# 2_mpcie.net
KiCad netlist of a schematic drawn in Altium Designer
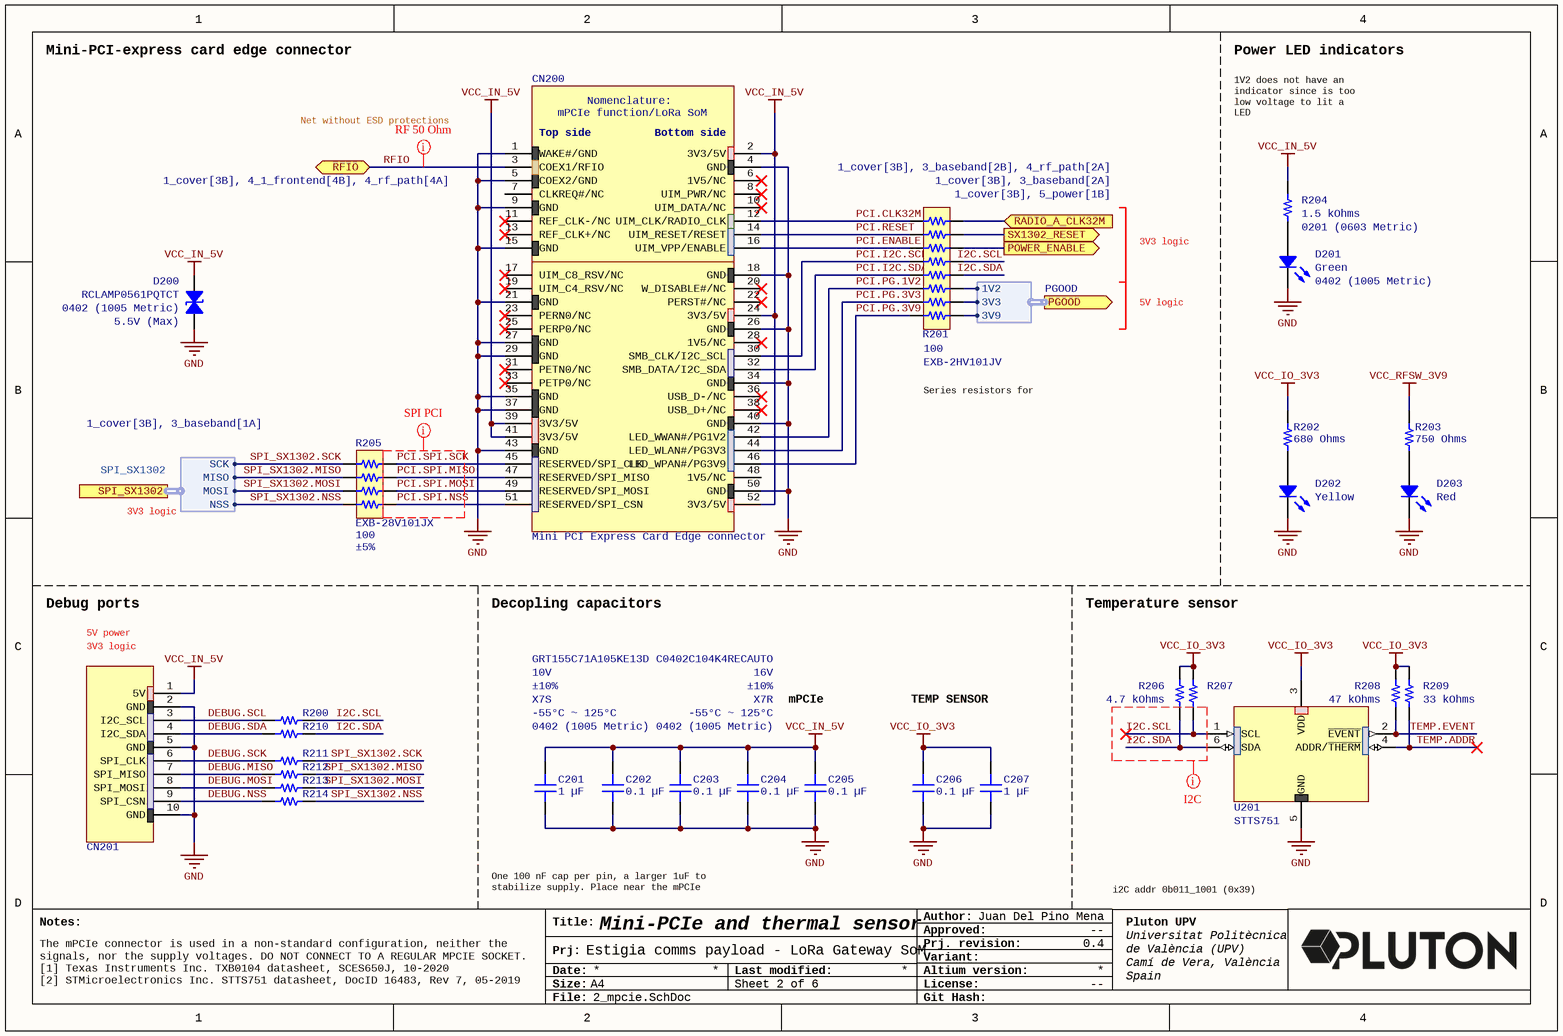
[diagram p0: 2_mpcie.SchDoc]

(export (version "E")
  (design (tool "Eeschema 10.0.6"))
  (components
    (comp (ref "C201")
      (value "1 µF")
      (footprint "CAP 0402_1005")
      (description "CAP CER 1UF 10V X7S 0402")
      (fields
        (field (name "PART NUMBER") "GRT155C71A105KE13D")
        (field (name "DEVICE PACKAGE") "0402 (1005 Metric)")
        (field (name "MANUFACTURER") "Murata Electronics")
        (field (name "OPERATING TEMPERATURE") "-55°C ~ 125°C")
        (field (name "TEMPERATURE COEFFICIENT") "X7S")
        (field (name "TOLERANCE") "±10%")
        (field (name "VOLTAGE - RATED") "10V")
      )
      (libsource (lib "Celestial Altium Library - altium_library") (part "Capacitor"))
    )
    (comp (ref "C202")
      (value "0.1 µF")
      (footprint "CAP 0402_1005")
      (description "CAP CER 0402 0.1UF 16V X7R 10%")
      (fields
        (field (name "PART NUMBER") "C0402C104K4RECAUTO")
        (field (name "MANUFACTURER") "KEMET")
        (field (name "OPERATING TEMPERATURE") "-55°C ~ 125°C")
        (field (name "PACKAGE / CASE") "0402 (1005 Metric)")
        (field (name "TEMPERATURE COEFFICIENT") "X7R")
        (field (name "TOLERANCE") "±10%")
        (field (name "VOLTAGE - RATED") "16V")
      )
      (libsource (lib "Celestial Altium Library - altium_library") (part "Capacitor"))
    )
    (comp (ref "C203")
      (value "0.1 µF")
      (footprint "CAP 0402_1005")
      (description "CAP CER 0402 0.1UF 16V X7R 10%")
      (fields (field (name "PART NUMBER") "C0402C104K4RECAUTO") (field (name "MANUFACTURER") "KEMET"))
      (libsource (lib "Celestial Altium Library - altium_library") (part "Capacitor"))
    )
    (comp (ref "C204")
      (value "0.1 µF")
      (footprint "CAP 0402_1005")
      (description "CAP CER 0402 0.1UF 16V X7R 10%")
      (fields (field (name "PART NUMBER") "C0402C104K4RECAUTO") (field (name "MANUFACTURER") "KEMET"))
      (libsource (lib "Celestial Altium Library - altium_library") (part "Capacitor"))
    )
    (comp (ref "C205")
      (value "0.1 µF")
      (footprint "CAP 0402_1005")
      (description "CAP CER 0402 0.1UF 16V X7R 10%")
      (fields (field (name "PART NUMBER") "C0402C104K4RECAUTO") (field (name "MANUFACTURER") "KEMET"))
      (libsource (lib "Celestial Altium Library - altium_library") (part "Capacitor"))
    )
    (comp (ref "C206")
      (value "0.1 µF")
      (footprint "CAP 0402_1005")
      (description "CAP CER 0402 0.1UF 16V X7R 10%")
      (fields (field (name "PART NUMBER") "C0402C104K4RECAUTO") (field (name "MANUFACTURER") "KEMET"))
      (libsource (lib "Celestial Altium Library - altium_library") (part "Capacitor"))
    )
    (comp (ref "C207")
      (value "1 µF")
      (footprint "CAP 0402_1005")
      (description "CAP CER 1UF 10V X7S 0402")
      (fields
        (field (name "PART NUMBER") "GRT155C71A105KE13D")
        (field (name "MANUFACTURER") "Murata Electronics")
      )
      (libsource (lib "Celestial Altium Library - altium_library") (part "Capacitor"))
    )
    (comp (ref "CN200")
      (value "Mini PCI Express Card Edge connector")
      (footprint "mpcie:Mini PCI Express")
      (libsource (lib "mpcie") (part "MiniPCIe Card"))
    )
    (comp (ref "CN201")
      (value "~")
      (footprint "connectors:header 1x10 2.54mm")
      (description "Specific debug port for the LoRa gateway SoM")
      (libsource (lib "connectors") (part "SoM debug header"))
    )
    (comp (ref "D200")
      (value "RCLAMP0561PQTCT")
      (footprint "0402")
      (description "1-LINE 5V 0.15PF 1.1R ESD SLP100")
      (fields
        (field (name "PART NUMBER") "RCLAMP0561PQTCT")
        (field (name "DEVICE PACKAGE") "0402 (1005 Metric)")
        (field (name "MANUFACTURER") "Semtech Corporation")
        (field (name "VOLTAGE - REVERSE STANDOFF (TYP)") "5.5V (Max)")
      )
      (libsource (lib "Celestial Altium Library - altium_library") (part "Diode TVS"))
    )
    (comp (ref "D201")
      (value "Green")
      (footprint "LED 0402_1005 GREEN")
      (description "LED GREEN CLEAR 2SMD")
      (fields
        (field (name "PART NUMBER") "EAST10052GA0")
        (field (name "COLOR") "Green")
        (field (name "DEVICE PACKAGE") "0402 (1005 Metric)")
        (field (name "MANUFACTURER") "Everlight Electronics Co Ltd")
      )
      (libsource (lib "Celestial Altium Library - altium_library") (part "LED"))
    )
    (comp (ref "D202")
      (value "Yellow")
      (footprint "LED 0402_1005 YELLOW")
      (description "LED YELLOW CLEAR 1005 SMD")
      (fields
        (field (name "PART NUMBER") "FHY1105P-TR")
        (field (name "COLOR") "Yellow")
        (field (name "MANUFACTURER") "Stanley Electric Co")
      )
      (libsource (lib "Celestial Altium Library - altium_library") (part "LED"))
    )
    (comp (ref "D203")
      (value "Red")
      (footprint "LED 0402_1005 RED")
      (description "LED RED CLEAR 2SMD")
      (fields
        (field (name "PART NUMBER") "EAST10053RA0")
        (field (name "COLOR") "Red")
        (field (name "MANUFACTURER") "Everlight Electronics Co Ltd")
      )
      (libsource (lib "Celestial Altium Library - altium_library") (part "LED"))
    )
    (comp (ref "R200")
      (value "0 Ohms")
      (footprint "RES 0201_0603")
      (description "RES SMD 0 OHM JUMPER 1/20W 0201")
      (fields (field (name "PART NUMBER") "AC0201JR-070RL") (field (name "MANUFACTURER") "Yageo"))
      (libsource (lib "Celestial Altium Library - altium_library") (part "Resistor"))
    )
    (comp (ref "R201")
      (value "EXB-2HV101JV")
      (footprint "RESNET 1506-16 CONVEX")
      (description "RES ARRAY 8 RES 100 OHM 1506")
      (fields
        (field (name "PART NUMBER") "EXB-2HV101JV")
        (field (name "MANUFACTURER") "Panasonic Electronic Components")
        (field (name "RESISTANCE (OHMS)") "100")
        (field (name "TOLERANCE") "±5%")
      )
      (libsource (lib "Celestial Altium Library - altium_library") (part "Resistor Array (8 Circuit)"))
    )
    (comp (ref "R202")
      (value "680 Ohms")
      (footprint "RES 0201_0603")
      (description "RES 680 OHM 5% 1/20W 0201")
      (fields (field (name "PART NUMBER") "RC0201JR-07680RL") (field (name "MANUFACTURER") "Yageo"))
      (libsource (lib "Celestial Altium Library - altium_library") (part "Resistor"))
    )
    (comp (ref "R203")
      (value "750 Ohms")
      (footprint "RES 0201_0603")
      (description "RES 750 OHM 5% 1/20W 0201")
      (fields (field (name "PART NUMBER") "RC0201JR-07750RL") (field (name "MANUFACTURER") "Yageo"))
      (libsource (lib "Celestial Altium Library - altium_library") (part "Resistor"))
    )
    (comp (ref "R204")
      (value "1.5 kOhms")
      (footprint "RES 0201_0603")
      (description "RES SMD 1.5K OHM 5% 1/20W 0201")
      (fields
        (field (name "PART NUMBER") "CRCW02011K50JNED")
        (field (name "DEVICE PACKAGE") "0201 (0603 Metric)")
        (field (name "MANUFACTURER") "Vishay Dale")
      )
      (libsource (lib "Celestial Altium Library - altium_library") (part "Resistor"))
    )
    (comp (ref "R205")
      (value "EXB-28V101JX")
      (footprint "RESNET 0804-8 CONVEX")
      (description "RES ARRAY 4 RES 100 OHM 0804")
      (fields
        (field (name "MANUFACTURER") "Panasonic Electronic Components")
        (field (name "PART NUMBER") "EXB-28V101JX")
        (field (name "RESISTANCE (OHMS)") "100")
        (field (name "TOLERANCE") "±5%")
      )
      (libsource (lib "passives") (part "Resistor Array (4 circuit)"))
    )
    (comp (ref "R206")
      (value "4.7 kOhms")
      (footprint "RES 0201_0603")
      (description "RES SMD 4.7K OHM 1% 1/20W 0201")
      (fields (field (name "PART NUMBER") "AC0201FR-074K7L") (field (name "MANUFACTURER") "Yageo"))
      (libsource (lib "Celestial Altium Library - altium_library") (part "Resistor"))
    )
    (comp (ref "R207")
      (value "4.7 kOhms")
      (footprint "RES 0201_0603")
      (description "RES SMD 4.7K OHM 1% 1/20W 0201")
      (fields (field (name "PART NUMBER") "AC0201FR-074K7L") (field (name "MANUFACTURER") "Yageo"))
      (libsource (lib "Celestial Altium Library - altium_library") (part "Resistor"))
    )
    (comp (ref "R208")
      (value "47 kOhms")
      (footprint "RES 0201_0603")
      (description "RES SMD 47K OHM 1% 1/20W 0201")
      (fields (field (name "PART NUMBER") "AC0201FR-0747KL") (field (name "MANUFACTURER") "Yageo"))
      (libsource (lib "Celestial Altium Library - altium_library") (part "Resistor"))
    )
    (comp (ref "R209")
      (value "33 kOhms")
      (footprint "RES 0201_0603")
      (description "RES SMD 33K OHM 1% 1/20W 0201")
      (fields (field (name "PART NUMBER") "CRCW020133K0FKED") (field (name "MANUFACTURER") "Vishay Dale"))
      (libsource (lib "Celestial Altium Library - altium_library") (part "Resistor"))
    )
    (comp (ref "R210")
      (value "0 Ohms")
      (footprint "RES 0201_0603")
      (description "RES SMD 0 OHM JUMPER 1/20W 0201")
      (fields (field (name "PART NUMBER") "AC0201JR-070RL") (field (name "MANUFACTURER") "Yageo"))
      (libsource (lib "Celestial Altium Library - altium_library") (part "Resistor"))
    )
    (comp (ref "R211")
      (value "0 Ohms")
      (footprint "RES 0201_0603")
      (description "RES SMD 0 OHM JUMPER 1/20W 0201")
      (fields (field (name "PART NUMBER") "AC0201JR-070RL") (field (name "MANUFACTURER") "Yageo"))
      (libsource (lib "Celestial Altium Library - altium_library") (part "Resistor"))
    )
    (comp (ref "R212")
      (value "0 Ohms")
      (footprint "RES 0201_0603")
      (description "RES SMD 0 OHM JUMPER 1/20W 0201")
      (fields (field (name "PART NUMBER") "AC0201JR-070RL") (field (name "MANUFACTURER") "Yageo"))
      (libsource (lib "Celestial Altium Library - altium_library") (part "Resistor"))
    )
    (comp (ref "R213")
      (value "0 Ohms")
      (footprint "RES 0201_0603")
      (description "RES SMD 0 OHM JUMPER 1/20W 0201")
      (fields (field (name "PART NUMBER") "AC0201JR-070RL") (field (name "MANUFACTURER") "Yageo"))
      (libsource (lib "Celestial Altium Library - altium_library") (part "Resistor"))
    )
    (comp (ref "R214")
      (value "0 Ohms")
      (footprint "RES 0201_0603")
      (description "RES SMD 0 OHM JUMPER 1/20W 0201")
      (fields (field (name "PART NUMBER") "AC0201JR-070RL") (field (name "MANUFACTURER") "Yageo"))
      (libsource (lib "Celestial Altium Library - altium_library") (part "Resistor"))
    )
    (comp (ref "U201")
      (value "STTS751")
      (footprint "ics:UDFN-6L")
      (description "2.25 V low-voltage local digital temperature sensor")
      (libsource (lib "sensors") (part "STTS751"))
    )
  )
  (nets
    (net (code "3") (name "/1V2") (class "Default")
      (node (ref "R201") (pin "11") (pinfunction "11_11") (pintype "passive"))
    )
    (net (code "4") (name "/3V3") (class "Default")
      (node (ref "R201") (pin "10") (pinfunction "10_10") (pintype "passive"))
    )
    (net (code "5") (name "/3V9") (class "Default")
      (node (ref "R201") (pin "9") (pinfunction "9_9") (pintype "passive"))
    )
    (net (code "6") (name "/DEBUG.MISO") (class "Default")
      (node (ref "CN201") (pin "7") (pinfunction "SPI_MISO_7") (pintype "passive"))
      (node (ref "R212") (pin "1") (pinfunction "1_1") (pintype "passive"))
    )
    (net (code "7") (name "/DEBUG.MOSI") (class "Default")
      (node (ref "CN201") (pin "8") (pinfunction "SPI_MOSI_8") (pintype "passive"))
      (node (ref "R213") (pin "1") (pinfunction "1_1") (pintype "passive"))
    )
    (net (code "8") (name "/DEBUG.NSS") (class "Default")
      (node (ref "CN201") (pin "9") (pinfunction "SPI_CSN_9") (pintype "passive"))
      (node (ref "R214") (pin "1") (pinfunction "1_1") (pintype "passive"))
    )
    (net (code "9") (name "/DEBUG.SCK") (class "Default")
      (node (ref "CN201") (pin "6") (pinfunction "SPI_CLK_6") (pintype "passive"))
      (node (ref "R211") (pin "1") (pinfunction "1_1") (pintype "passive"))
    )
    (net (code "10") (name "/DEBUG.SCL") (class "Default")
      (node (ref "CN201") (pin "3") (pinfunction "I2C_SCL_3") (pintype "passive"))
      (node (ref "R200") (pin "1") (pinfunction "1_1") (pintype "passive"))
    )
    (net (code "11") (name "/DEBUG.SDA") (class "Default")
      (node (ref "CN201") (pin "4") (pinfunction "I2C_SDA_4") (pintype "passive"))
      (node (ref "R210") (pin "1") (pinfunction "1_1") (pintype "passive"))
    )
    (net (code "12") (name "/I2C.SCL") (class "Default")
      (node (ref "R200") (pin "2") (pinfunction "2_2") (pintype "passive"))
      (node (ref "R201") (pin "13") (pinfunction "13_13") (pintype "passive"))
      (node (ref "R207") (pin "1") (pinfunction "1_1") (pintype "passive"))
      (node (ref "U201") (pin "1") (pinfunction "SCL_1") (pintype "input"))
    )
    (net (code "13") (name "/I2C.SDA") (class "Default")
      (node (ref "R201") (pin "12") (pinfunction "12_12") (pintype "passive"))
      (node (ref "R206") (pin "1") (pinfunction "1_1") (pintype "passive"))
      (node (ref "R210") (pin "2") (pinfunction "2_2") (pintype "passive"))
      (node (ref "U201") (pin "6") (pinfunction "SDA_6") (pintype "bidirectional"))
    )
    (net (code "14") (name "/PCI.CLK32M") (class "Default")
      (node (ref "CN200") (pin "12") (pinfunction "UIM_CLK/RADIO_CLK_12") (pintype "passive"))
      (node (ref "R201") (pin "1") (pinfunction "1_1") (pintype "passive"))
    )
    (net (code "15") (name "/PCI.ENABLE") (class "Default")
      (node (ref "CN200") (pin "16") (pinfunction "UIM_VPP/ENABLE_16") (pintype "passive"))
      (node (ref "R201") (pin "3") (pinfunction "3_3") (pintype "passive"))
    )
    (net (code "16") (name "/PCI.I2C.SCL") (class "Default")
      (node (ref "CN200") (pin "30") (pinfunction "SMB_CLK/I2C_SCL_30") (pintype "passive"))
      (node (ref "R201") (pin "4") (pinfunction "4_4") (pintype "passive"))
    )
    (net (code "17") (name "/PCI.I2C.SDA") (class "Default")
      (node (ref "CN200") (pin "32") (pinfunction "SMB_DATA/I2C_SDA_32") (pintype "passive"))
      (node (ref "R201") (pin "5") (pinfunction "6_5") (pintype "passive"))
    )
    (net (code "18") (name "/PCI.PG.1V2") (class "Default")
      (node (ref "CN200") (pin "42") (pinfunction "LED_WWAN#/PG1V2_42") (pintype "passive"))
      (node (ref "R201") (pin "6") (pinfunction "6_6") (pintype "passive"))
    )
    (net (code "19") (name "/PCI.PG.3V3") (class "Default")
      (node (ref "CN200") (pin "44") (pinfunction "LED_WLAN#/PG3V3_44") (pintype "passive"))
      (node (ref "R201") (pin "7") (pinfunction "7_7") (pintype "passive"))
    )
    (net (code "20") (name "/PCI.PG.3V9") (class "Default")
      (node (ref "CN200") (pin "46") (pinfunction "LED_WPAN#/PG3V9_46") (pintype "passive"))
      (node (ref "R201") (pin "8") (pinfunction "8_8") (pintype "passive"))
    )
    (net (code "21") (name "/PCI.RESET") (class "Default")
      (node (ref "CN200") (pin "14") (pinfunction "UIM_RESET/RESET_14") (pintype "passive"))
      (node (ref "R201") (pin "2") (pinfunction "2_2") (pintype "passive"))
    )
    (net (code "22") (name "/PCI.SPI.MISO") (class "Default")
      (node (ref "CN200") (pin "47") (pinfunction "RESERVED/SPI_MISO_47") (pintype "passive"))
      (node (ref "R205") (pin "6") (pinfunction "6_6") (pintype "passive"))
    )
    (net (code "23") (name "/PCI.SPI.MOSI") (class "Default")
      (node (ref "CN200") (pin "49") (pinfunction "RESERVED/SPI_MOSI_49") (pintype "passive"))
      (node (ref "R205") (pin "7") (pinfunction "7_7") (pintype "passive"))
    )
    (net (code "24") (name "/PCI.SPI.NSS") (class "Default")
      (node (ref "CN200") (pin "51") (pinfunction "RESERVED/SPI_CSN_51") (pintype "passive"))
      (node (ref "R205") (pin "8") (pinfunction "8_8") (pintype "passive"))
    )
    (net (code "25") (name "/PCI.SPI.SCK") (class "Default")
      (node (ref "CN200") (pin "45") (pinfunction "RESERVED/SPI_CLK_45") (pintype "passive"))
      (node (ref "R205") (pin "5") (pinfunction "5_5") (pintype "passive"))
    )
    (net (code "26") (name "/POWER_ENABLE") (class "Default")
      (node (ref "R201") (pin "14") (pinfunction "14_14") (pintype "passive"))
    )
    (net (code "27") (name "/RADIO_A_CLK32M") (class "Default")
      (node (ref "R201") (pin "16") (pinfunction "16_16") (pintype "passive"))
    )
    (net (code "28") (name "/RFIO") (class "Default")
      (node (ref "CN200") (pin "3") (pinfunction "COEX1/RFIO_3") (pintype "passive"))
    )
    (net (code "29") (name "/SPI_SX1302.MISO") (class "Default")
      (node (ref "R205") (pin "3") (pinfunction "3_3") (pintype "passive"))
      (node (ref "R212") (pin "2") (pinfunction "2_2") (pintype "passive"))
    )
    (net (code "30") (name "/SPI_SX1302.MOSI") (class "Default")
      (node (ref "R205") (pin "2") (pinfunction "2_2") (pintype "passive"))
      (node (ref "R213") (pin "2") (pinfunction "2_2") (pintype "passive"))
    )
    (net (code "31") (name "/SPI_SX1302.NSS") (class "Default")
      (node (ref "R205") (pin "1") (pinfunction "1_1") (pintype "passive"))
      (node (ref "R214") (pin "2") (pinfunction "2_2") (pintype "passive"))
    )
    (net (code "32") (name "/SPI_SX1302.SCK") (class "Default")
      (node (ref "R205") (pin "4") (pinfunction "4_4") (pintype "passive"))
      (node (ref "R211") (pin "2") (pinfunction "2_2") (pintype "passive"))
    )
    (net (code "33") (name "/SX1302_RESET") (class "Default")
      (node (ref "R201") (pin "15") (pinfunction "15_15") (pintype "passive"))
    )
    (net (code "34") (name "/TEMP.ADDR") (class "Default")
      (node (ref "R209") (pin "1") (pinfunction "1_1") (pintype "passive"))
      (node (ref "U201") (pin "4") (pinfunction "ADDR/~{THERM}_4") (pintype "bidirectional"))
    )
    (net (code "35") (name "/TEMP.EVENT") (class "Default")
      (node (ref "R208") (pin "1") (pinfunction "1_1") (pintype "passive"))
      (node (ref "U201") (pin "2") (pinfunction "~{EVENT}_2") (pintype "output"))
    )
    (net (code "38") (name "GND") (class "Default")
      (node (ref "C201") (pin "1") (pinfunction "1_1") (pintype "passive"))
      (node (ref "C202") (pin "1") (pinfunction "1_1") (pintype "passive"))
      (node (ref "C203") (pin "1") (pinfunction "1_1") (pintype "passive"))
      (node (ref "C204") (pin "1") (pinfunction "1_1") (pintype "passive"))
      (node (ref "C205") (pin "1") (pinfunction "1_1") (pintype "passive"))
      (node (ref "C206") (pin "1") (pinfunction "1_1") (pintype "passive"))
      (node (ref "C207") (pin "1") (pinfunction "1_1") (pintype "passive"))
      (node (ref "CN200") (pin "1") (pinfunction "WAKE#/GND_1") (pintype "passive"))
      (node (ref "CN200") (pin "15") (pinfunction "GND_15") (pintype "power_in"))
      (node (ref "CN200") (pin "18") (pinfunction "GND_18") (pintype "power_in"))
      (node (ref "CN200") (pin "21") (pinfunction "GND_21") (pintype "power_in"))
      (node (ref "CN200") (pin "26") (pinfunction "GND_26") (pintype "power_in"))
      (node (ref "CN200") (pin "27") (pinfunction "GND_27") (pintype "power_in"))
      (node (ref "CN200") (pin "29") (pinfunction "GND_29") (pintype "power_in"))
      (node (ref "CN200") (pin "34") (pinfunction "GND_34") (pintype "power_in"))
      (node (ref "CN200") (pin "35") (pinfunction "GND_35") (pintype "power_in"))
      (node (ref "CN200") (pin "37") (pinfunction "GND_37") (pintype "power_in"))
      (node (ref "CN200") (pin "4") (pinfunction "GND_4") (pintype "power_in"))
      (node (ref "CN200") (pin "40") (pinfunction "GND_40") (pintype "power_in"))
      (node (ref "CN200") (pin "43") (pinfunction "GND_43") (pintype "power_in"))
      (node (ref "CN200") (pin "5") (pinfunction "COEX2/GND_5") (pintype "passive"))
      (node (ref "CN200") (pin "50") (pinfunction "GND_50") (pintype "power_in"))
      (node (ref "CN200") (pin "9") (pinfunction "GND_9") (pintype "power_in"))
      (node (ref "CN201") (pin "10") (pinfunction "GND_10") (pintype "power_in"))
      (node (ref "CN201") (pin "2") (pinfunction "GND_2") (pintype "power_in"))
      (node (ref "CN201") (pin "5") (pinfunction "GND_5") (pintype "power_in"))
      (node (ref "D200") (pin "1") (pinfunction "1_1") (pintype "passive"))
      (node (ref "D201") (pin "2") (pinfunction "2_2") (pintype "passive"))
      (node (ref "D202") (pin "2") (pinfunction "2_2") (pintype "passive"))
      (node (ref "D203") (pin "2") (pinfunction "2_2") (pintype "passive"))
      (node (ref "U201") (pin "5") (pinfunction "GND_5") (pintype "power_in"))
    )
    (net (code "39") (name "Net-(D201-Pad1)") (class "Default")
      (node (ref "D201") (pin "1") (pinfunction "1_1") (pintype "passive"))
      (node (ref "R204") (pin "1") (pinfunction "1_1") (pintype "passive"))
    )
    (net (code "40") (name "Net-(D202-Pad1)") (class "Default")
      (node (ref "D202") (pin "1") (pinfunction "1_1") (pintype "passive"))
      (node (ref "R202") (pin "1") (pinfunction "1_1") (pintype "passive"))
    )
    (net (code "41") (name "Net-(D203-Pad1)") (class "Default")
      (node (ref "D203") (pin "1") (pinfunction "1_1") (pintype "passive"))
      (node (ref "R203") (pin "1") (pinfunction "1_1") (pintype "passive"))
    )
    (net (code "42") (name "VCC_IN_5V") (class "Default")
      (node (ref "C201") (pin "2") (pinfunction "2_2") (pintype "passive"))
      (node (ref "C202") (pin "2") (pinfunction "2_2") (pintype "passive"))
      (node (ref "C203") (pin "2") (pinfunction "2_2") (pintype "passive"))
      (node (ref "C204") (pin "2") (pinfunction "2_2") (pintype "passive"))
      (node (ref "C205") (pin "2") (pinfunction "2_2") (pintype "passive"))
      (node (ref "CN200") (pin "2") (pinfunction "3V3/5V_2") (pintype "passive"))
      (node (ref "CN200") (pin "24") (pinfunction "3V3/5V_24") (pintype "passive"))
      (node (ref "CN200") (pin "39") (pinfunction "3V3/5V_39") (pintype "passive"))
      (node (ref "CN200") (pin "41") (pinfunction "3V3/5V_41") (pintype "passive"))
      (node (ref "CN200") (pin "52") (pinfunction "3V3/5V_52") (pintype "passive"))
      (node (ref "CN201") (pin "1") (pinfunction "5V_1") (pintype "power_in"))
      (node (ref "D200") (pin "2") (pinfunction "2_2") (pintype "passive"))
      (node (ref "R204") (pin "2") (pinfunction "2_2") (pintype "passive"))
    )
    (net (code "43") (name "VCC_IO_3V3") (class "Default")
      (node (ref "C206") (pin "2") (pinfunction "2_2") (pintype "passive"))
      (node (ref "C207") (pin "2") (pinfunction "2_2") (pintype "passive"))
      (node (ref "R202") (pin "2") (pinfunction "2_2") (pintype "passive"))
      (node (ref "R206") (pin "2") (pinfunction "2_2") (pintype "passive"))
      (node (ref "R207") (pin "2") (pinfunction "2_2") (pintype "passive"))
      (node (ref "R208") (pin "2") (pinfunction "2_2") (pintype "passive"))
      (node (ref "R209") (pin "2") (pinfunction "2_2") (pintype "passive"))
      (node (ref "U201") (pin "3") (pinfunction "VDD_3") (pintype "power_in"))
    )
    (net (code "44") (name "VCC_RFSW_3V9") (class "Default")
      (node (ref "R203") (pin "2") (pinfunction "2_2") (pintype "passive"))
    )
    (net (code "45") (name "unconnected-(CN200-1V5{slash}NC-Pad6)") (class "Default")
      (node (ref "CN200") (pin "6") (pinfunction "1V5/NC_6") (pintype "passive+no_connect"))
    )
    (net (code "46") (name "unconnected-(CN200-1V5{slash}NC-Pad28)") (class "Default")
      (node (ref "CN200") (pin "28") (pinfunction "1V5/NC_28") (pintype "power_in+no_connect"))
    )
    (net (code "47") (name "unconnected-(CN200-1V5{slash}NC-Pad48)") (class "Default")
      (node (ref "CN200") (pin "48") (pinfunction "1V5/NC_48") (pintype "passive"))
    )
    (net (code "48") (name "unconnected-(CN200-CLKREQ#{slash}NC-Pad7)") (class "Default")
      (node (ref "CN200") (pin "7") (pinfunction "CLKREQ#/NC_7") (pintype "passive"))
    )
    (net (code "49") (name "unconnected-(CN200-PERN0{slash}NC-Pad23)") (class "Default")
      (node (ref "CN200") (pin "23") (pinfunction "PERN0/NC_23") (pintype "passive+no_connect"))
    )
    (net (code "50") (name "unconnected-(CN200-PERP0{slash}NC-Pad25)") (class "Default")
      (node (ref "CN200") (pin "25") (pinfunction "PERP0/NC_25") (pintype "passive+no_connect"))
    )
    (net (code "51") (name "unconnected-(CN200-PERST#{slash}NC-Pad22)") (class "Default")
      (node (ref "CN200") (pin "22") (pinfunction "PERST#/NC_22") (pintype "passive+no_connect"))
    )
    (net (code "52") (name "unconnected-(CN200-PETN0{slash}NC-Pad31)") (class "Default")
      (node (ref "CN200") (pin "31") (pinfunction "PETN0/NC_31") (pintype "passive+no_connect"))
    )
    (net (code "53") (name "unconnected-(CN200-PETP0{slash}NC-Pad33)") (class "Default")
      (node (ref "CN200") (pin "33") (pinfunction "PETP0/NC_33") (pintype "passive+no_connect"))
    )
    (net (code "54") (name "unconnected-(CN200-REF_CLK+{slash}NC-Pad13)") (class "Default")
      (node (ref "CN200") (pin "13") (pinfunction "REF_CLK+/NC_13") (pintype "passive+no_connect"))
    )
    (net (code "55") (name "unconnected-(CN200-REF_CLK-{slash}NC-Pad11)") (class "Default")
      (node (ref "CN200") (pin "11") (pinfunction "REF_CLK-/NC_11") (pintype "passive+no_connect"))
    )
    (net (code "56") (name "unconnected-(CN200-UIM_C4_RSV{slash}NC-Pad19)") (class "Default")
      (node (ref "CN200") (pin "19") (pinfunction "UIM_C4_RSV/NC_19") (pintype "passive+no_connect"))
    )
    (net (code "57") (name "unconnected-(CN200-UIM_C8_RSV{slash}NC-Pad17)") (class "Default")
      (node (ref "CN200") (pin "17") (pinfunction "UIM_C8_RSV/NC_17") (pintype "passive+no_connect"))
    )
    (net (code "58") (name "unconnected-(CN200-UIM_DATA{slash}NC-Pad10)") (class "Default")
      (node (ref "CN200") (pin "10") (pinfunction "UIM_DATA/NC_10") (pintype "passive+no_connect"))
    )
    (net (code "59") (name "unconnected-(CN200-UIM_PWR{slash}NC-Pad8)") (class "Default")
      (node (ref "CN200") (pin "8") (pinfunction "UIM_PWR/NC_8") (pintype "passive+no_connect"))
    )
    (net (code "60") (name "unconnected-(CN200-USB_D+{slash}NC-Pad38)") (class "Default")
      (node (ref "CN200") (pin "38") (pinfunction "USB_D+/NC_38") (pintype "passive+no_connect"))
    )
    (net (code "61") (name "unconnected-(CN200-USB_D-{slash}NC-Pad36)") (class "Default")
      (node (ref "CN200") (pin "36") (pinfunction "USB_D-/NC_36") (pintype "passive+no_connect"))
    )
    (net (code "62") (name "unconnected-(CN200-W_DISABLE#{slash}NC-Pad20)") (class "Default")
      (node (ref "CN200") (pin "20") (pinfunction "W_DISABLE#/NC_20") (pintype "passive+no_connect"))
    )
  )
)
